# Schema_Proiect_v116.net
KiCad netlist of a schematic drawn in EAGLE
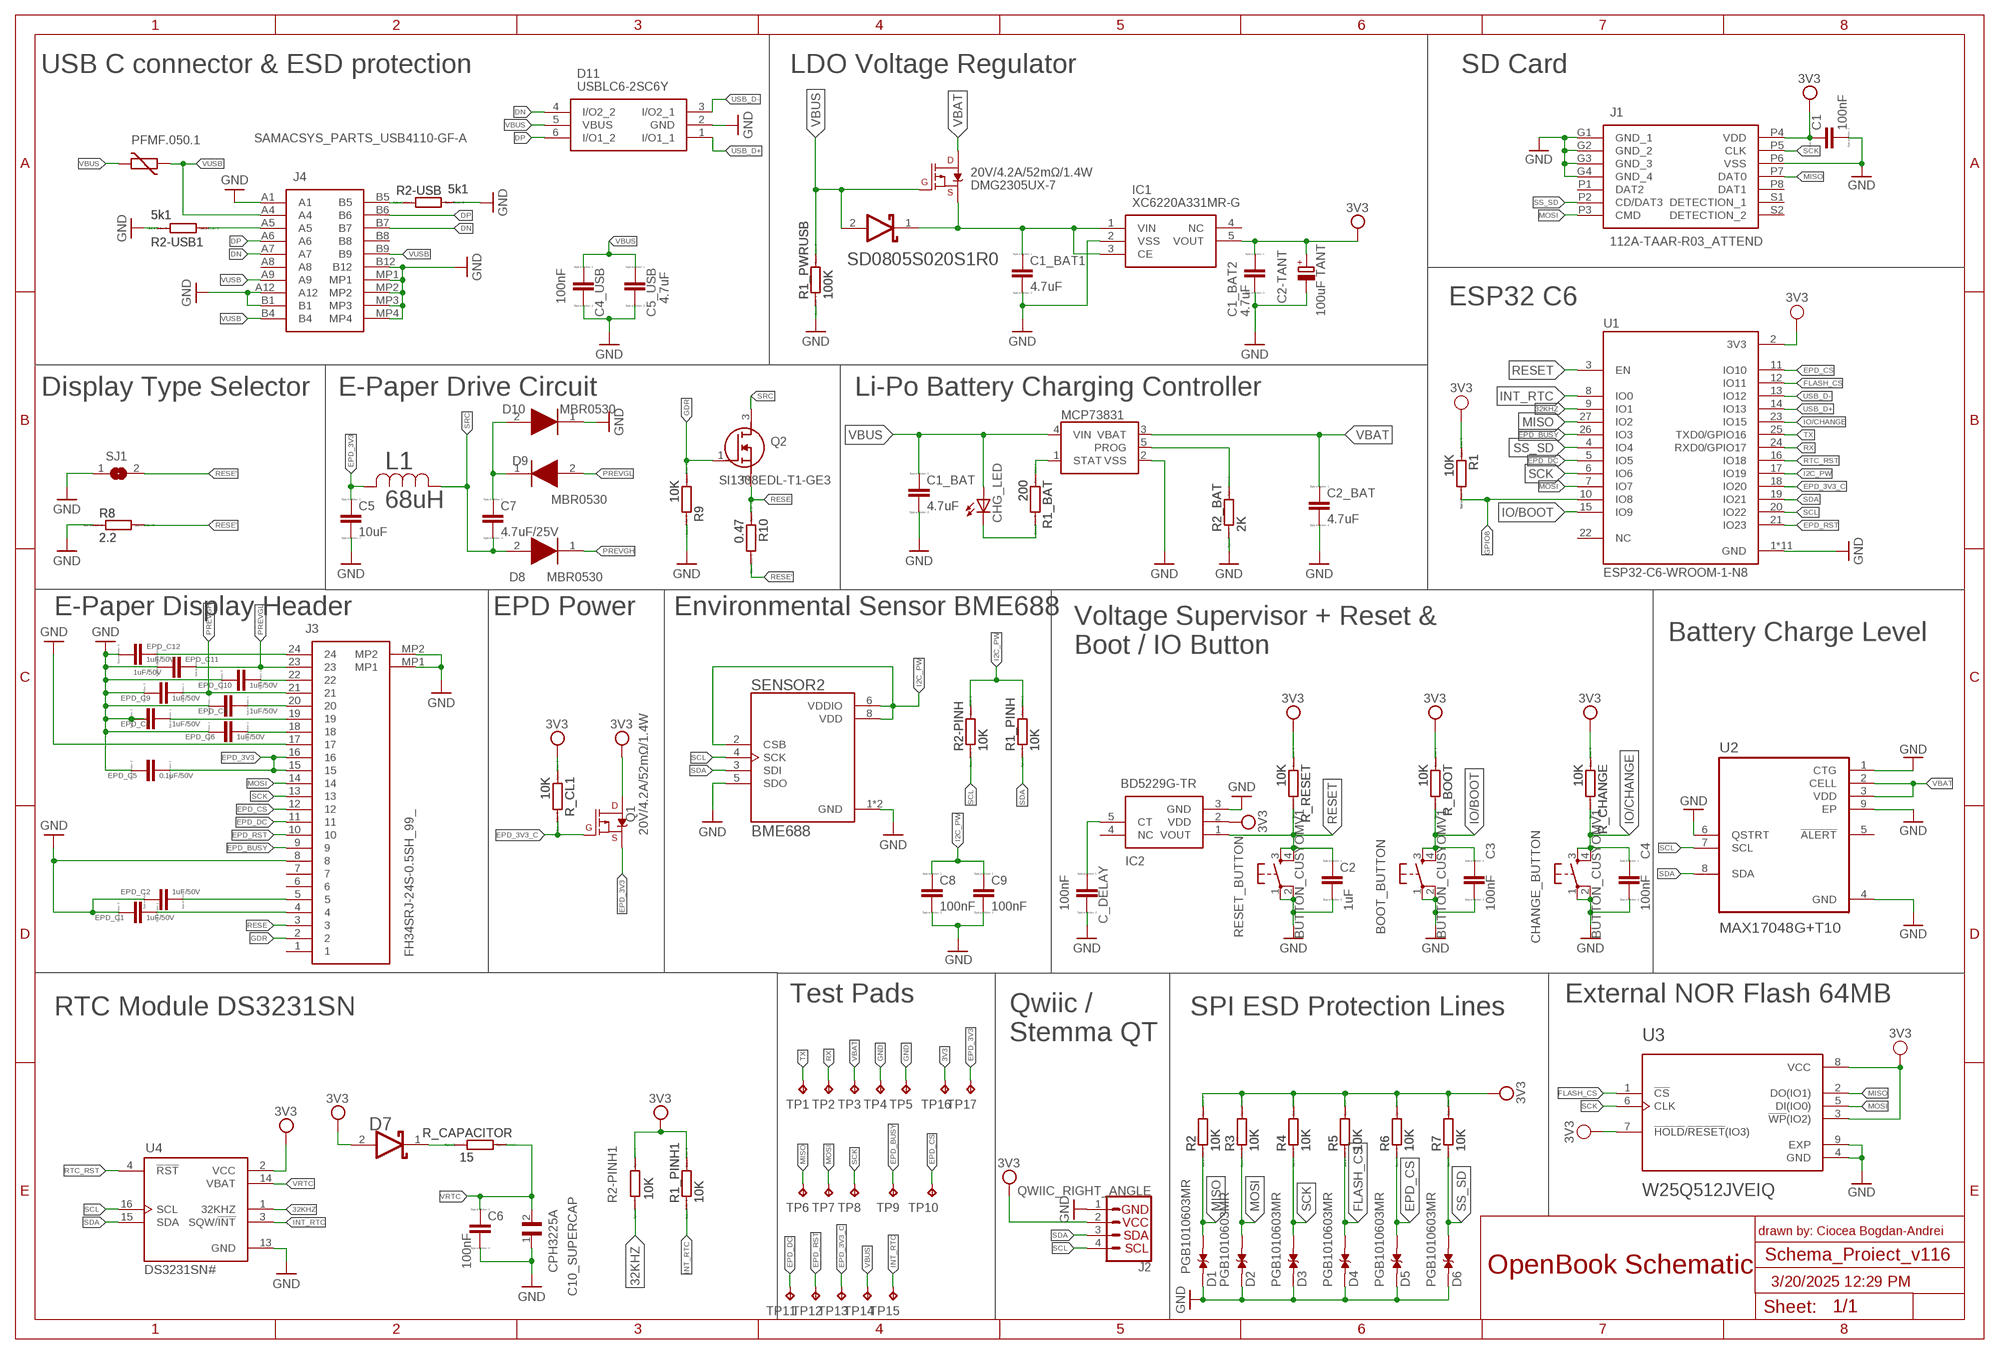
[diagram p0: schematic, sheet 1]

(export (version "E")
  (design (tool "Eeschema 10.0.6"))
  (components
    (comp (ref "BOOT_BUTTON")
      (value "BUTTON_CUSYOMV1")
      (footprint "eagle-import:MYBUTTON")
      (libsource (lib "eagle-import") (part "BUTTON_CUSYOMV1"))
    )
    (comp (ref "C1")
      (value "100nF")
      (footprint "eagle-import:EAGLE-LTSPICE_C0402")
      (libsource (lib "eagle-import") (part "EAGLE-LTSPICE_CC0402"))
    )
    (comp (ref "C1_BAT")
      (value "4.7uF")
      (footprint "eagle-import:EAGLE-LTSPICE_C0402")
      (libsource (lib "eagle-import") (part "EAGLE-LTSPICE_CC0402"))
    )
    (comp (ref "C1_BAT1")
      (value "4.7uF")
      (footprint "eagle-import:EAGLE-LTSPICE_C0402")
      (libsource (lib "eagle-import") (part "EAGLE-LTSPICE_CC0402"))
    )
    (comp (ref "C1_BAT2")
      (value "4.7uF")
      (footprint "eagle-import:EAGLE-LTSPICE_C0402")
      (libsource (lib "eagle-import") (part "EAGLE-LTSPICE_CC0402"))
    )
    (comp (ref "C2")
      (value "1uF")
      (footprint "eagle-import:EAGLE-LTSPICE_C0402")
      (libsource (lib "eagle-import") (part "EAGLE-LTSPICE_CC0402"))
    )
    (comp (ref "C2-TANT")
      (value "100uF TANT")
      (footprint "eagle-import:RCL_CT3528")
      (libsource (lib "eagle-import") (part "RCL_CPOL-EUCT3528"))
    )
    (comp (ref "C2_BAT")
      (value "4.7uF")
      (footprint "eagle-import:EAGLE-LTSPICE_C0402")
      (libsource (lib "eagle-import") (part "EAGLE-LTSPICE_CC0402"))
    )
    (comp (ref "C3")
      (value "100nF")
      (footprint "eagle-import:EAGLE-LTSPICE_C0402")
      (libsource (lib "eagle-import") (part "EAGLE-LTSPICE_CC0402"))
    )
    (comp (ref "C4")
      (value "100nF")
      (footprint "eagle-import:EAGLE-LTSPICE_C0402")
      (libsource (lib "eagle-import") (part "EAGLE-LTSPICE_CC0402"))
    )
    (comp (ref "C4_USB")
      (value "100nF")
      (footprint "eagle-import:EAGLE-LTSPICE_C0402")
      (libsource (lib "eagle-import") (part "EAGLE-LTSPICE_CC0402"))
    )
    (comp (ref "C5")
      (value "10uF")
      (footprint "eagle-import:EAGLE-LTSPICE_C0402")
      (libsource (lib "eagle-import") (part "EAGLE-LTSPICE_CC0402"))
    )
    (comp (ref "C5_USB")
      (value "4.7uF")
      (footprint "eagle-import:EAGLE-LTSPICE_C0402")
      (libsource (lib "eagle-import") (part "EAGLE-LTSPICE_CC0402"))
    )
    (comp (ref "C6")
      (value "100nF")
      (footprint "eagle-import:EAGLE-LTSPICE_C0402")
      (libsource (lib "eagle-import") (part "EAGLE-LTSPICE_CC0402"))
    )
    (comp (ref "C7")
      (value "4.7uF/25V")
      (footprint "eagle-import:EAGLE-LTSPICE_C0402")
      (libsource (lib "eagle-import") (part "EAGLE-LTSPICE_CC0402"))
    )
    (comp (ref "C8")
      (value "100nF")
      (footprint "eagle-import:EAGLE-LTSPICE_C0402")
      (libsource (lib "eagle-import") (part "EAGLE-LTSPICE_CC0402"))
    )
    (comp (ref "C9")
      (value "100nF")
      (footprint "eagle-import:EAGLE-LTSPICE_C0402")
      (libsource (lib "eagle-import") (part "EAGLE-LTSPICE_CC0402"))
    )
    (comp (ref "C10_SUPERCAP")
      (value "CPH3225A")
      (footprint "eagle-import:CAPCP3225X100N")
      (fields (field (name "MF") "Seiko Instruments"))
      (libsource (lib "eagle-import") (part "CPH3225A"))
    )
    (comp (ref "CHANGE_BUTTON")
      (value "BUTTON_CUSYOMV1")
      (footprint "eagle-import:MYBUTTON")
      (libsource (lib "eagle-import") (part "BUTTON_CUSYOMV1"))
    )
    (comp (ref "CHG_LED")
      (value "ADAFRUIT_LEDCHIP-LED0603")
      (footprint "eagle-import:ADAFRUIT_CHIP-LED0603")
      (libsource (lib "eagle-import") (part "ADAFRUIT_LEDCHIP-LED0603"))
    )
    (comp (ref "C_DELAY")
      (value "100nF")
      (footprint "eagle-import:EAGLE-LTSPICE_C0402")
      (libsource (lib "eagle-import") (part "EAGLE-LTSPICE_CC0402"))
    )
    (comp (ref "D1")
      (value "PGB1010603MR")
      (footprint "eagle-import:DIOC1608X36N")
      (fields (field (name "MF") "Littelfuse Inc."))
      (libsource (lib "eagle-import") (part "PGB1010603MR"))
    )
    (comp (ref "D2")
      (value "PGB1010603MR")
      (footprint "eagle-import:DIOC1608X36N")
      (fields (field (name "MF") "Littelfuse Inc."))
      (libsource (lib "eagle-import") (part "PGB1010603MR"))
    )
    (comp (ref "D3")
      (value "PGB1010603MR")
      (footprint "eagle-import:DIOC1608X36N")
      (fields (field (name "MF") "Littelfuse Inc."))
      (libsource (lib "eagle-import") (part "PGB1010603MR"))
    )
    (comp (ref "D4")
      (value "PGB1010603MR")
      (footprint "eagle-import:DIOC1608X36N")
      (fields (field (name "MF") "Littelfuse Inc."))
      (libsource (lib "eagle-import") (part "PGB1010603MR"))
    )
    (comp (ref "D5")
      (value "PGB1010603MR")
      (footprint "eagle-import:DIOC1608X36N")
      (fields (field (name "MF") "Littelfuse Inc."))
      (libsource (lib "eagle-import") (part "PGB1010603MR"))
    )
    (comp (ref "D6")
      (value "PGB1010603MR")
      (footprint "eagle-import:DIOC1608X36N")
      (fields (field (name "MF") "Littelfuse Inc."))
      (libsource (lib "eagle-import") (part "PGB1010603MR"))
    )
    (comp (ref "D7")
      (value "SD0805S020S1R0")
      (footprint "eagle-import:ESP32_WROVER_AVX---SD0805S020S1R0_AVX_SD0805S020S1R0_0")
      (fields
        (field (name "DIGIKEY_PART_NUMBER") "478-7800-1-ND")
        (field (name "MF") "AVX")
        (field (name "MOUSER_PART_NUMBER") "581-SD0805S020S1R0")
      )
      (libsource (lib "eagle-import") (part "ESP32_WROVER_AVX---SD0805S020S1R0_AVX_SD0805S020S1R0_0_0AVX_SD0805S020S1R0_0_0"))
    )
    (comp (ref "D8")
      (value "MBR0530")
      (footprint "eagle-import:SOD3716X135N")
      (fields (field (name "MF") "ON Semiconductor"))
      (libsource (lib "eagle-import") (part "MBR0530"))
    )
    (comp (ref "D9")
      (value "MBR0530")
      (footprint "eagle-import:SOD3716X135N")
      (fields (field (name "MF") "ON Semiconductor"))
      (libsource (lib "eagle-import") (part "MBR0530"))
    )
    (comp (ref "D10")
      (value "MBR0530")
      (footprint "eagle-import:SOD3716X135N")
      (fields (field (name "MF") "ON Semiconductor"))
      (libsource (lib "eagle-import") (part "MBR0530"))
    )
    (comp (ref "D11")
      (value "USBLC6-2SC6Y")
      (footprint "eagle-import:SOT95P280X145-6N")
      (fields (field (name "MF") "STMicroelectronics"))
      (libsource (lib "eagle-import") (part "USBLC6-2SC6Y"))
    )
    (comp (ref "DMG2305UX-7")
      (value "20V/4.2A/52mΩ/1.4W")
      (footprint "eagle-import:ESP32_WROVER_SPARKFUN-DISCRETESEMI_SOT23-3")
      (libsource (lib "eagle-import") (part "ESP32_WROVER_SPARKFUN-DISCRETESEMI_MOSFET_PCH-DMG2305UX-7"))
    )
    (comp (ref "EPD_C1")
      (value "1uF/50V")
      (footprint "eagle-import:EAGLE-LTSPICE_C0402")
      (libsource (lib "eagle-import") (part "EAGLE-LTSPICE_CC0402"))
    )
    (comp (ref "EPD_C2")
      (value "1uF/50V")
      (footprint "eagle-import:EAGLE-LTSPICE_C0402")
      (libsource (lib "eagle-import") (part "EAGLE-LTSPICE_CC0402"))
    )
    (comp (ref "EPD_C5")
      (value "0.1uF/50V")
      (footprint "eagle-import:EAGLE-LTSPICE_C0402")
      (libsource (lib "eagle-import") (part "EAGLE-LTSPICE_CC0402"))
    )
    (comp (ref "EPD_C6")
      (value "1uF/50V")
      (footprint "eagle-import:EAGLE-LTSPICE_C0402")
      (libsource (lib "eagle-import") (part "EAGLE-LTSPICE_CC0402"))
    )
    (comp (ref "EPD_C7")
      (value "1uF/50V")
      (footprint "eagle-import:EAGLE-LTSPICE_C0402")
      (libsource (lib "eagle-import") (part "EAGLE-LTSPICE_CC0402"))
    )
    (comp (ref "EPD_C8")
      (value "1uF/50V")
      (footprint "eagle-import:EAGLE-LTSPICE_C0402")
      (libsource (lib "eagle-import") (part "EAGLE-LTSPICE_CC0402"))
    )
    (comp (ref "EPD_C9")
      (value "1uF/50V")
      (footprint "eagle-import:EAGLE-LTSPICE_C0402")
      (libsource (lib "eagle-import") (part "EAGLE-LTSPICE_CC0402"))
    )
    (comp (ref "EPD_C10")
      (value "1uF/50V")
      (footprint "eagle-import:EAGLE-LTSPICE_C0402")
      (libsource (lib "eagle-import") (part "EAGLE-LTSPICE_CC0402"))
    )
    (comp (ref "EPD_C11")
      (value "1uF/50V")
      (footprint "eagle-import:EAGLE-LTSPICE_C0402")
      (libsource (lib "eagle-import") (part "EAGLE-LTSPICE_CC0402"))
    )
    (comp (ref "EPD_C12")
      (value "1uF/50V")
      (footprint "eagle-import:EAGLE-LTSPICE_C0402")
      (libsource (lib "eagle-import") (part "EAGLE-LTSPICE_CC0402"))
    )
    (comp (ref "IC1")
      (value "XC6220A331MR-G")
      (footprint "eagle-import:SOT95P280X120-5N")
      (fields (field (name "MOUSER_PART_NUMBER") "865-XC6220A331MR-G"))
      (libsource (lib "eagle-import") (part "XC6220A331MR-G"))
    )
    (comp (ref "IC2")
      (value "BD5229G-TR")
      (footprint "eagle-import:SOT95P280X125-5N")
      (fields (field (name "MOUSER_PART_NUMBER") "755-BD5229G-TR"))
      (libsource (lib "eagle-import") (part "BD5229G-TR"))
    )
    (comp (ref "J1")
      (value "112A-TAAR-R03_ATTEND")
      (footprint "eagle-import:112ATAARR03ATTEND")
      (fields (field (name "MANUFACTURER_PART_NUMBER") "112A-TAAR-R03 ATTEND"))
      (libsource (lib "eagle-import") (part "112A-TAAR-R03_ATTEND"))
    )
    (comp (ref "J2")
      (value "QWIIC_RIGHT_ANGLE")
      (footprint "eagle-import:JST04_1MM_RA")
      (libsource (lib "eagle-import") (part "QWIIC_CONNECTORJS-1MM"))
    )
    (comp (ref "J3")
      (value "FH34SRJ-24S-0.5SH_99_")
      (footprint "eagle-import:FH34SRJ24S05SH99")
      (fields
        (field (name "MANUFACTURER_PART_NUMBER") "FH34SRJ-24S-0.5SH(99)")
        (field (name "MOUSER_PART_NUMBER") "798-FH34SRJ24S05SH99")
      )
      (libsource (lib "eagle-import") (part "FH34SRJ-24S-0.5SH_99_"))
    )
    (comp (ref "J4")
      (value "SAMACSYS_PARTS_USB4110-GF-A")
      (footprint "eagle-import:SAMACSYS_PARTS_USB4110GFA")
      (fields
        (field (name "MANUFACTURER_PART_NUMBER") "USB4110-GF-A")
        (field (name "MOUSER_PART_NUMBER") "640-USB4110-GF-A")
      )
      (libsource (lib "eagle-import") (part "SAMACSYS_PARTS_USB4110-GF-A"))
    )
    (comp (ref "L1")
      (value "68uH")
      (footprint "eagle-import:IND_4828-WE-TPC_WRE")
      (fields
        (field (name "MANUFACTURER_PART_NUMBER") "744043680")
        (field (name "COPYRIGHT") "Copyright (C) 2024 Ultra Librarian. All rights reserved.")
      )
      (libsource (lib "eagle-import") (part "744043680IND_4828-WE-TPC_WRE"))
    )
    (comp (ref "MCP73831")
      (value "ESP32_WROVER_SPARKFUN-IC-POWER_MCP73831")
      (footprint "eagle-import:ESP32_WROVER_SPARKFUN-IC-POWER_SOT23-5")
      (libsource (lib "eagle-import") (part "ESP32_WROVER_SPARKFUN-IC-POWER_MCP73831"))
    )
    (comp (ref "PFMF.050.1")
      (value "ESP32C6_VARISTORCN1812")
      (footprint "eagle-import:ESP32C6_VARISTOR_CT_CN1812")
      (libsource (lib "eagle-import") (part "ESP32C6_VARISTORCN1812"))
    )
    (comp (ref "Q1")
      (value "20V/4.2A/52mΩ/1.4W")
      (footprint "eagle-import:ESP32_WROVER_SPARKFUN-DISCRETESEMI_SOT23-3")
      (libsource (lib "eagle-import") (part "ESP32_WROVER_SPARKFUN-DISCRETESEMI_MOSFET_PCH-DMG2305UX-7"))
    )
    (comp (ref "Q2")
      (value "SI1308EDL-T1-GE3")
      (footprint "eagle-import:SOT65P210X110-3N")
      (fields (field (name "MF") "Vishay Siliconix"))
      (libsource (lib "eagle-import") (part "SI1308EDL-T1-GE3"))
    )
    (comp (ref "R1")
      (value "10K")
      (footprint "eagle-import:ESP32_WROVER_EAGLE-LTSPICE_R0402")
      (libsource (lib "eagle-import") (part "ESP32_WROVER_EAGLE-LTSPICE_RR0402"))
    )
    (comp (ref "R1_BAT")
      (value "200")
      (footprint "eagle-import:ESP32_WROVER_EAGLE-LTSPICE_R0402")
      (libsource (lib "eagle-import") (part "ESP32_WROVER_EAGLE-LTSPICE_RR0402"))
    )
    (comp (ref "R1_PINH")
      (value "10K")
      (footprint "eagle-import:ESP32_WROVER_EAGLE-LTSPICE_R0402")
      (libsource (lib "eagle-import") (part "ESP32_WROVER_EAGLE-LTSPICE_RR0402"))
    )
    (comp (ref "R1_PINH1")
      (value "10K")
      (footprint "eagle-import:ESP32_WROVER_EAGLE-LTSPICE_R0402")
      (libsource (lib "eagle-import") (part "ESP32_WROVER_EAGLE-LTSPICE_RR0402"))
    )
    (comp (ref "R1_PWRUSB")
      (value "100K")
      (footprint "eagle-import:ESP32_WROVER_EAGLE-LTSPICE_R0402")
      (libsource (lib "eagle-import") (part "ESP32_WROVER_EAGLE-LTSPICE_RR0402"))
    )
    (comp (ref "R2")
      (value "10K")
      (footprint "eagle-import:ESP32_WROVER_EAGLE-LTSPICE_R0402")
      (libsource (lib "eagle-import") (part "ESP32_WROVER_EAGLE-LTSPICE_RR0402"))
    )
    (comp (ref "R2-PINH")
      (value "10K")
      (footprint "eagle-import:ESP32_WROVER_EAGLE-LTSPICE_R0402")
      (libsource (lib "eagle-import") (part "ESP32_WROVER_EAGLE-LTSPICE_RR0402"))
    )
    (comp (ref "R2-PINH1")
      (value "10K")
      (footprint "eagle-import:ESP32_WROVER_EAGLE-LTSPICE_R0402")
      (libsource (lib "eagle-import") (part "ESP32_WROVER_EAGLE-LTSPICE_RR0402"))
    )
    (comp (ref "R2-USB")
      (value "5k1")
      (footprint "eagle-import:ESP32_WROVER_EAGLE-LTSPICE_R0402")
      (libsource (lib "eagle-import") (part "ESP32_WROVER_EAGLE-LTSPICE_RR0402"))
    )
    (comp (ref "R2-USB1")
      (value "5k1")
      (footprint "eagle-import:ESP32_WROVER_EAGLE-LTSPICE_R0402")
      (libsource (lib "eagle-import") (part "ESP32_WROVER_EAGLE-LTSPICE_RR0402"))
    )
    (comp (ref "R2_BAT")
      (value "2K")
      (footprint "eagle-import:ESP32_WROVER_EAGLE-LTSPICE_R0402")
      (libsource (lib "eagle-import") (part "ESP32_WROVER_EAGLE-LTSPICE_RR0402"))
    )
    (comp (ref "R3")
      (value "10K")
      (footprint "eagle-import:ESP32_WROVER_EAGLE-LTSPICE_R0402")
      (libsource (lib "eagle-import") (part "ESP32_WROVER_EAGLE-LTSPICE_RR0402"))
    )
    (comp (ref "R4")
      (value "10K")
      (footprint "eagle-import:ESP32_WROVER_EAGLE-LTSPICE_R0402")
      (libsource (lib "eagle-import") (part "ESP32_WROVER_EAGLE-LTSPICE_RR0402"))
    )
    (comp (ref "R5")
      (value "10K")
      (footprint "eagle-import:ESP32_WROVER_EAGLE-LTSPICE_R0402")
      (libsource (lib "eagle-import") (part "ESP32_WROVER_EAGLE-LTSPICE_RR0402"))
    )
    (comp (ref "R6")
      (value "10K")
      (footprint "eagle-import:ESP32_WROVER_EAGLE-LTSPICE_R0402")
      (libsource (lib "eagle-import") (part "ESP32_WROVER_EAGLE-LTSPICE_RR0402"))
    )
    (comp (ref "R7")
      (value "10K")
      (footprint "eagle-import:ESP32_WROVER_EAGLE-LTSPICE_R0402")
      (libsource (lib "eagle-import") (part "ESP32_WROVER_EAGLE-LTSPICE_RR0402"))
    )
    (comp (ref "R8")
      (value "2.2")
      (footprint "eagle-import:ESP32_WROVER_EAGLE-LTSPICE_R0402")
      (libsource (lib "eagle-import") (part "ESP32_WROVER_EAGLE-LTSPICE_RR0402"))
    )
    (comp (ref "R9")
      (value "10K")
      (footprint "eagle-import:ESP32_WROVER_EAGLE-LTSPICE_R0402")
      (libsource (lib "eagle-import") (part "ESP32_WROVER_EAGLE-LTSPICE_RR0402"))
    )
    (comp (ref "R10")
      (value "0.47")
      (footprint "eagle-import:ESP32_WROVER_EAGLE-LTSPICE_R0402")
      (libsource (lib "eagle-import") (part "ESP32_WROVER_EAGLE-LTSPICE_RR0402"))
    )
    (comp (ref "RESET_BUTTON")
      (value "BUTTON_CUSYOMV1")
      (footprint "eagle-import:MYBUTTON")
      (libsource (lib "eagle-import") (part "BUTTON_CUSYOMV1"))
    )
    (comp (ref "R_BOOT")
      (value "10K")
      (footprint "eagle-import:ESP32_WROVER_EAGLE-LTSPICE_R0402")
      (libsource (lib "eagle-import") (part "ESP32_WROVER_EAGLE-LTSPICE_RR0402"))
    )
    (comp (ref "R_CAPACITOR")
      (value "15")
      (footprint "eagle-import:ESP32_WROVER_EAGLE-LTSPICE_R0402")
      (libsource (lib "eagle-import") (part "ESP32_WROVER_EAGLE-LTSPICE_RR0402"))
    )
    (comp (ref "R_CHANGE")
      (value "10K")
      (footprint "eagle-import:ESP32_WROVER_EAGLE-LTSPICE_R0402")
      (libsource (lib "eagle-import") (part "ESP32_WROVER_EAGLE-LTSPICE_RR0402"))
    )
    (comp (ref "R_CL1")
      (value "10K")
      (footprint "eagle-import:ESP32_WROVER_EAGLE-LTSPICE_R0402")
      (libsource (lib "eagle-import") (part "ESP32_WROVER_EAGLE-LTSPICE_RR0402"))
    )
    (comp (ref "R_RESET")
      (value "10K")
      (footprint "eagle-import:ESP32_WROVER_EAGLE-LTSPICE_R0402")
      (libsource (lib "eagle-import") (part "ESP32_WROVER_EAGLE-LTSPICE_RR0402"))
    )
    (comp (ref "SD0805S020S1R0")
      (value "ESP32_WROVER_AVX---SD0805S020S1R0_AVX_SD0805S020S1R0_0_0AVX_SD0805S020S1R0_0_0")
      (footprint "eagle-import:ESP32_WROVER_AVX---SD0805S020S1R0_AVX_SD0805S020S1R0_0")
      (fields
        (field (name "DIGIKEY_PART_NUMBER") "478-7800-1-ND")
        (field (name "MF") "AVX")
        (field (name "MOUSER_PART_NUMBER") "581-SD0805S020S1R0")
      )
      (libsource (lib "eagle-import") (part "ESP32_WROVER_AVX---SD0805S020S1R0_AVX_SD0805S020S1R0_0_0AVX_SD0805S020S1R0_0_0"))
    )
    (comp (ref "SENSOR2")
      (value "BME688")
      (footprint "eagle-import:ESP32_WROVER_BME680_PSON80P300X300X100-8N")
      (fields (field (name "MF") "Bosch Sensortec") (field (name "MP") "BME680"))
      (libsource (lib "eagle-import") (part "ESP32_WROVER_BME680_BME680"))
    )
    (comp (ref "SJ1") (value "SJ") (footprint "eagle-import:SJ") (libsource (lib "eagle-import") (part "SJ")))
    (comp (ref "TP1")
      (value "TX")
      (footprint "eagle-import:TP20R")
      (libsource (lib "eagle-import") (part "TPTP20R"))
    )
    (comp (ref "TP2")
      (value "RX")
      (footprint "eagle-import:TP20R")
      (libsource (lib "eagle-import") (part "TPTP20R"))
    )
    (comp (ref "TP3")
      (value "VBAT")
      (footprint "eagle-import:TP20R")
      (libsource (lib "eagle-import") (part "TPTP20R"))
    )
    (comp (ref "TP4")
      (value "GND")
      (footprint "eagle-import:TP20R")
      (libsource (lib "eagle-import") (part "TPTP20R"))
    )
    (comp (ref "TP5")
      (value "GND")
      (footprint "eagle-import:TP20R")
      (libsource (lib "eagle-import") (part "TPTP20R"))
    )
    (comp (ref "TP6")
      (value "MISO")
      (footprint "eagle-import:TP20R")
      (libsource (lib "eagle-import") (part "TPTP20R"))
    )
    (comp (ref "TP7")
      (value "MOSI")
      (footprint "eagle-import:TP20R")
      (libsource (lib "eagle-import") (part "TPTP20R"))
    )
    (comp (ref "TP8")
      (value "SCK")
      (footprint "eagle-import:TP20R")
      (libsource (lib "eagle-import") (part "TPTP20R"))
    )
    (comp (ref "TP9")
      (value "EPD_BUSY")
      (footprint "eagle-import:TP20R")
      (libsource (lib "eagle-import") (part "TPTP20R"))
    )
    (comp (ref "TP10")
      (value "EPD_CS")
      (footprint "eagle-import:TP20R")
      (libsource (lib "eagle-import") (part "TPTP20R"))
    )
    (comp (ref "TP11")
      (value "EPD_DC")
      (footprint "eagle-import:TP20R")
      (libsource (lib "eagle-import") (part "TPTP20R"))
    )
    (comp (ref "TP12")
      (value "EPD_RST")
      (footprint "eagle-import:TP20R")
      (libsource (lib "eagle-import") (part "TPTP20R"))
    )
    (comp (ref "TP13")
      (value "EPD_3V3_C")
      (footprint "eagle-import:TP20R")
      (libsource (lib "eagle-import") (part "TPTP20R"))
    )
    (comp (ref "TP14")
      (value "VBUS")
      (footprint "eagle-import:TP20R")
      (libsource (lib "eagle-import") (part "TPTP20R"))
    )
    (comp (ref "TP15")
      (value "INT_RTC")
      (footprint "eagle-import:TP20R")
      (libsource (lib "eagle-import") (part "TPTP20R"))
    )
    (comp (ref "TP16")
      (value "3V3")
      (footprint "eagle-import:TP20R")
      (libsource (lib "eagle-import") (part "TPTP20R"))
    )
    (comp (ref "TP17")
      (value "EPD_3V3")
      (footprint "eagle-import:TP20R")
      (libsource (lib "eagle-import") (part "TPTP20R"))
    )
    (comp (ref "U1")
      (value "ESP32-C6-WROOM-1-N8")
      (footprint "eagle-import:XCVR_ESP32-C6-WROOM-1-N8")
      (fields (field (name "MF") "Espressif Systems"))
      (libsource (lib "eagle-import") (part "ESP32-C6-WROOM-1-N8"))
    )
    (comp (ref "U2")
      (value "MAX17048G+T10")
      (footprint "eagle-import:SON50P200X200X80-9N")
      (fields (field (name "MF") "Analog Devices"))
      (libsource (lib "eagle-import") (part "MAX17048G+T10"))
    )
    (comp (ref "U3")
      (value "W25Q512JVEIQ")
      (footprint "eagle-import:SON127P600X800X80-9N")
      (fields (field (name "MF") "Winbond Electronics"))
      (libsource (lib "eagle-import") (part "W25Q512JVEIQ"))
    )
    (comp (ref "U4")
      (value "DS3231SN#")
      (footprint "eagle-import:SOIC127P1032X265-16N")
      (fields (field (name "MF") "Analog Devices"))
      (libsource (lib "eagle-import") (part "DS3231SN#"))
    )
  )
  (nets
    (net (code "1") (name "3V3") (class "Default")
      (node (ref "C1") (pin "1") (pinfunction "1_1") (pintype "passive"))
      (node (ref "C1_BAT2") (pin "1") (pinfunction "1_1") (pintype "passive"))
      (node (ref "C2-TANT") (pin "+") (pinfunction "+_+") (pintype "passive"))
      (node (ref "D7") (pin "2") (pinfunction "ANODE_2") (pintype "bidirectional"))
      (node (ref "IC1") (pin "5") (pinfunction "VOUT_5") (pintype "bidirectional"))
      (node (ref "IC2") (pin "2") (pinfunction "VDD_2") (pintype "bidirectional"))
      (node (ref "J1") (pin "P4") (pinfunction "VDD_P4") (pintype "bidirectional"))
      (node (ref "J2") (pin "2") (pinfunction "2_2") (pintype "power_in"))
      (node (ref "Q1") (pin "3") (pinfunction "D_3") (pintype "bidirectional"))
      (node (ref "R1") (pin "1") (pinfunction "1_1") (pintype "passive"))
      (node (ref "R1_PINH1") (pin "2") (pinfunction "2_2") (pintype "passive"))
      (node (ref "R2") (pin "2") (pinfunction "2_2") (pintype "passive"))
      (node (ref "R2-PINH1") (pin "1") (pinfunction "1_1") (pintype "passive"))
      (node (ref "R3") (pin "2") (pinfunction "2_2") (pintype "passive"))
      (node (ref "R4") (pin "2") (pinfunction "2_2") (pintype "passive"))
      (node (ref "R5") (pin "2") (pinfunction "2_2") (pintype "passive"))
      (node (ref "R6") (pin "2") (pinfunction "2_2") (pintype "passive"))
      (node (ref "R7") (pin "2") (pinfunction "2_2") (pintype "passive"))
      (node (ref "R_BOOT") (pin "1") (pinfunction "1_1") (pintype "passive"))
      (node (ref "R_CHANGE") (pin "1") (pinfunction "1_1") (pintype "passive"))
      (node (ref "R_CL1") (pin "1") (pinfunction "1_1") (pintype "passive"))
      (node (ref "R_RESET") (pin "1") (pinfunction "1_1") (pintype "passive"))
      (node (ref "TP16") (pin "TP") (pinfunction "TP_TP") (pintype "input"))
      (node (ref "U1") (pin "2") (pinfunction "3V3_2") (pintype "power_in"))
      (node (ref "U3") (pin "3") (pinfunction "~{WP}(IO2)_3") (pintype "bidirectional"))
      (node (ref "U3") (pin "7") (pinfunction "~{HOLD}/~{RESET}(IO3)_7") (pintype "bidirectional"))
      (node (ref "U3") (pin "8") (pinfunction "VCC_8") (pintype "power_in"))
      (node (ref "U4") (pin "2") (pinfunction "VCC_2") (pintype "power_in"))
    )
    (net (code "2") (name "32KHZ") (class "Default")
      (node (ref "R2-PINH1") (pin "2") (pinfunction "2_2") (pintype "passive"))
      (node (ref "U1") (pin "9") (pinfunction "IO1_9") (pintype "bidirectional"))
      (node (ref "U4") (pin "1") (pinfunction "32KHZ_1") (pintype "output"))
    )
    (net (code "3") (name "DN") (class "Default")
      (node (ref "D11") (pin "4") (pinfunction "I/O2_2_4") (pintype "bidirectional"))
      (node (ref "J4") (pin "A7") (pinfunction "A7_A7") (pintype "bidirectional"))
      (node (ref "J4") (pin "B7") (pinfunction "B7_B7") (pintype "bidirectional"))
    )
    (net (code "4") (name "DP") (class "Default")
      (node (ref "D11") (pin "6") (pinfunction "I/O1_2_6") (pintype "bidirectional"))
      (node (ref "J4") (pin "A6") (pinfunction "A6_A6") (pintype "bidirectional"))
      (node (ref "J4") (pin "B6") (pinfunction "B6_B6") (pintype "bidirectional"))
    )
    (net (code "5") (name "EPD_3V3") (class "Default")
      (node (ref "C5") (pin "1") (pinfunction "1_1") (pintype "passive"))
      (node (ref "EPD_C5") (pin "1") (pinfunction "1_1") (pintype "passive"))
      (node (ref "J3") (pin "15") (pinfunction "15_15") (pintype "bidirectional"))
      (node (ref "J3") (pin "16") (pinfunction "16_16") (pintype "bidirectional"))
      (node (ref "L1") (pin "2") (pinfunction "2_2") (pintype "passive"))
      (node (ref "Q1") (pin "2") (pinfunction "S_2") (pintype "bidirectional"))
      (node (ref "TP17") (pin "TP") (pinfunction "TP_TP") (pintype "input"))
    )
    (net (code "6") (name "EPD_3V3_C") (class "Default")
      (node (ref "Q1") (pin "1") (pinfunction "G_1") (pintype "bidirectional"))
      (node (ref "R_CL1") (pin "2") (pinfunction "2_2") (pintype "passive"))
      (node (ref "TP13") (pin "TP") (pinfunction "TP_TP") (pintype "input"))
      (node (ref "U1") (pin "18") (pinfunction "IO20_18") (pintype "bidirectional"))
    )
    (net (code "7") (name "EPD_BUSY") (class "Default")
      (node (ref "J3") (pin "9") (pinfunction "9_9") (pintype "bidirectional"))
      (node (ref "TP9") (pin "TP") (pinfunction "TP_TP") (pintype "input"))
      (node (ref "U1") (pin "26") (pinfunction "IO3_26") (pintype "bidirectional"))
    )
    (net (code "8") (name "EPD_CS") (class "Default")
      (node (ref "D5") (pin "2") (pinfunction "2_2") (pintype "passive"))
      (node (ref "J3") (pin "12") (pinfunction "12_12") (pintype "bidirectional"))
      (node (ref "R6") (pin "1") (pinfunction "1_1") (pintype "passive"))
      (node (ref "TP10") (pin "TP") (pinfunction "TP_TP") (pintype "input"))
      (node (ref "U1") (pin "11") (pinfunction "IO10_11") (pintype "bidirectional"))
    )
    (net (code "9") (name "EPD_DC") (class "Default")
      (node (ref "J3") (pin "11") (pinfunction "11_11") (pintype "bidirectional"))
      (node (ref "TP11") (pin "TP") (pinfunction "TP_TP") (pintype "input"))
      (node (ref "U1") (pin "5") (pinfunction "IO5_5") (pintype "bidirectional"))
    )
    (net (code "10") (name "EPD_RST") (class "Default")
      (node (ref "J3") (pin "10") (pinfunction "10_10") (pintype "bidirectional"))
      (node (ref "TP12") (pin "TP") (pinfunction "TP_TP") (pintype "input"))
      (node (ref "U1") (pin "21") (pinfunction "IO23_21") (pintype "bidirectional"))
    )
    (net (code "11") (name "FLASH_CS") (class "Default")
      (node (ref "D4") (pin "2") (pinfunction "2_2") (pintype "passive"))
      (node (ref "R5") (pin "1") (pinfunction "1_1") (pintype "passive"))
      (node (ref "U1") (pin "12") (pinfunction "IO11_12") (pintype "bidirectional"))
      (node (ref "U3") (pin "1") (pinfunction "~{CS}_1") (pintype "input"))
    )
    (net (code "12") (name "GDR") (class "Default")
      (node (ref "J3") (pin "2") (pinfunction "2_2") (pintype "bidirectional"))
      (node (ref "Q2") (pin "1") (pinfunction "G_1") (pintype "bidirectional"))
      (node (ref "R9") (pin "1") (pinfunction "1_1") (pintype "passive"))
    )
    (net (code "13") (name "GND") (class "Default")
      (node (ref "BOOT_BUTTON") (pin "1") (pinfunction "1_1") (pintype "passive"))
      (node (ref "BOOT_BUTTON") (pin "2") (pinfunction "2_2") (pintype "passive"))
      (node (ref "C1") (pin "2") (pinfunction "2_2") (pintype "passive"))
      (node (ref "C10_SUPERCAP") (pin "1") (pinfunction "1_1") (pintype "passive"))
      (node (ref "C1_BAT") (pin "2") (pinfunction "2_2") (pintype "passive"))
      (node (ref "C1_BAT1") (pin "2") (pinfunction "2_2") (pintype "passive"))
      (node (ref "C1_BAT2") (pin "2") (pinfunction "2_2") (pintype "passive"))
      (node (ref "C2") (pin "2") (pinfunction "2_2") (pintype "passive"))
      (node (ref "C2-TANT") (pin "-") (pinfunction "-_-") (pintype "passive"))
      (node (ref "C2_BAT") (pin "2") (pinfunction "2_2") (pintype "passive"))
      (node (ref "C3") (pin "2") (pinfunction "2_2") (pintype "passive"))
      (node (ref "C4") (pin "2") (pinfunction "2_2") (pintype "passive"))
      (node (ref "C4_USB") (pin "2") (pinfunction "2_2") (pintype "passive"))
      (node (ref "C5") (pin "2") (pinfunction "2_2") (pintype "passive"))
      (node (ref "C5_USB") (pin "2") (pinfunction "2_2") (pintype "passive"))
      (node (ref "C6") (pin "2") (pinfunction "2_2") (pintype "passive"))
      (node (ref "C8") (pin "2") (pinfunction "2_2") (pintype "passive"))
      (node (ref "C9") (pin "2") (pinfunction "2_2") (pintype "passive"))
      (node (ref "CHANGE_BUTTON") (pin "1") (pinfunction "1_1") (pintype "passive"))
      (node (ref "CHANGE_BUTTON") (pin "2") (pinfunction "2_2") (pintype "passive"))
      (node (ref "C_DELAY") (pin "2") (pinfunction "2_2") (pintype "passive"))
      (node (ref "D1") (pin "1") (pinfunction "1_1") (pintype "passive"))
      (node (ref "D10") (pin "1") (pinfunction "K_1") (pintype "bidirectional"))
      (node (ref "D11") (pin "2") (pinfunction "GND_2") (pintype "bidirectional"))
      (node (ref "D2") (pin "1") (pinfunction "1_1") (pintype "passive"))
      (node (ref "D3") (pin "1") (pinfunction "1_1") (pintype "passive"))
      (node (ref "D4") (pin "1") (pinfunction "1_1") (pintype "passive"))
      (node (ref "D5") (pin "1") (pinfunction "1_1") (pintype "passive"))
      (node (ref "D6") (pin "1") (pinfunction "1_1") (pintype "passive"))
      (node (ref "EPD_C1") (pin "2") (pinfunction "2_2") (pintype "passive"))
      (node (ref "EPD_C10") (pin "2") (pinfunction "2_2") (pintype "passive"))
      (node (ref "EPD_C11") (pin "2") (pinfunction "2_2") (pintype "passive"))
      (node (ref "EPD_C12") (pin "2") (pinfunction "2_2") (pintype "passive"))
      (node (ref "EPD_C2") (pin "2") (pinfunction "2_2") (pintype "passive"))
      (node (ref "EPD_C5") (pin "2") (pinfunction "2_2") (pintype "passive"))
      (node (ref "EPD_C6") (pin "2") (pinfunction "2_2") (pintype "passive"))
      (node (ref "EPD_C7") (pin "2") (pinfunction "2_2") (pintype "passive"))
      (node (ref "EPD_C8") (pin "2") (pinfunction "2_2") (pintype "passive"))
      (node (ref "EPD_C9") (pin "2") (pinfunction "2_2") (pintype "passive"))
      (node (ref "IC1") (pin "2") (pinfunction "VSS_2") (pintype "bidirectional"))
      (node (ref "IC2") (pin "3") (pinfunction "GND_3") (pintype "bidirectional"))
      (node (ref "J1") (pin "G1") (pinfunction "GND_1_G1") (pintype "bidirectional"))
      (node (ref "J1") (pin "G2") (pinfunction "GND_2_G2") (pintype "bidirectional"))
      (node (ref "J1") (pin "G3") (pinfunction "GND_3_G3") (pintype "bidirectional"))
      (node (ref "J1") (pin "G4") (pinfunction "GND_4_G4") (pintype "bidirectional"))
      (node (ref "J1") (pin "P6") (pinfunction "VSS_P6") (pintype "bidirectional"))
      (node (ref "J2") (pin "1") (pinfunction "1_1") (pintype "power_in"))
      (node (ref "J3") (pin "17") (pinfunction "17_17") (pintype "bidirectional"))
      (node (ref "J3") (pin "8") (pinfunction "8_8") (pintype "bidirectional"))
      (node (ref "J3") (pin "MP1") (pinfunction "MP1_MP1") (pintype "bidirectional"))
      (node (ref "J3") (pin "MP2") (pinfunction "MP2_MP2") (pintype "bidirectional"))
      (node (ref "J4") (pin "A1") (pinfunction "A1_A1") (pintype "bidirectional"))
      (node (ref "J4") (pin "A12") (pinfunction "A12_A12") (pintype "bidirectional"))
      (node (ref "J4") (pin "B1") (pinfunction "B1_B1") (pintype "bidirectional"))
      (node (ref "J4") (pin "B12") (pinfunction "B12_B12") (pintype "bidirectional"))
      (node (ref "J4") (pin "MP1") (pinfunction "MP1_MP1") (pintype "bidirectional"))
      (node (ref "J4") (pin "MP2") (pinfunction "MP2_MP2") (pintype "bidirectional"))
      (node (ref "J4") (pin "MP3") (pinfunction "MP3_MP3") (pintype "bidirectional"))
      (node (ref "J4") (pin "MP4") (pinfunction "MP4_MP4") (pintype "bidirectional"))
      (node (ref "MCP73831") (pin "2") (pinfunction "VSS_2") (pintype "power_in"))
      (node (ref "R1_PWRUSB") (pin "1") (pinfunction "1_1") (pintype "passive"))
      (node (ref "R2-USB") (pin "2") (pinfunction "2_2") (pintype "passive"))
      (node (ref "R2-USB1") (pin "1") (pinfunction "1_1") (pintype "passive"))
      (node (ref "R2_BAT") (pin "1") (pinfunction "1_1") (pintype "passive"))
      (node (ref "R8") (pin "1") (pinfunction "1_1") (pintype "passive"))
      (node (ref "R9") (pin "2") (pinfunction "2_2") (pintype "passive"))
      (node (ref "RESET_BUTTON") (pin "1") (pinfunction "1_1") (pintype "passive"))
      (node (ref "RESET_BUTTON") (pin "2") (pinfunction "2_2") (pintype "passive"))
      (node (ref "SENSOR2") (pin "1") (pinfunction "GND_1") (pintype "power_in"))
      (node (ref "SENSOR2") (pin "5") (pinfunction "SDO_5") (pintype "bidirectional"))
      (node (ref "SENSOR2") (pin "7") (pinfunction "GND_7") (pintype "power_in"))
      (node (ref "SJ1") (pin "1") (pinfunction "1_1") (pintype "passive"))
      (node (ref "TP4") (pin "TP") (pinfunction "TP_TP") (pintype "input"))
      (node (ref "TP5") (pin "TP") (pinfunction "TP_TP") (pintype "input"))
      (node (ref "U1") (pin "1") (pinfunction "GND_1") (pintype "power_in"))
      (node (ref "U1") (pin "28") (pinfunction "GND_28") (pintype "power_in"))
      (node (ref "U1") (pin "29_1") (pinfunction "GND_29_1") (pintype "power_in"))
      (node (ref "U1") (pin "29_2") (pinfunction "GND_29_2") (pintype "power_in"))
      (node (ref "U1") (pin "29_3") (pinfunction "GND_29_3") (pintype "power_in"))
      (node (ref "U1") (pin "29_4") (pinfunction "GND_29_4") (pintype "power_in"))
      (node (ref "U1") (pin "29_5") (pinfunction "GND_29_5") (pintype "power_in"))
      (node (ref "U1") (pin "29_6") (pinfunction "GND_29_6") (pintype "power_in"))
      (node (ref "U1") (pin "29_7") (pinfunction "GND_29_7") (pintype "power_in"))
      (node (ref "U1") (pin "29_8") (pinfunction "GND_29_8") (pintype "power_in"))
      (node (ref "U1") (pin "29_9") (pinfunction "GND_29_9") (pintype "power_in"))
      (node (ref "U2") (pin "1") (pinfunction "CTG_1") (pintype "power_in"))
      (node (ref "U2") (pin "4") (pinfunction "GND_4") (pintype "power_in"))
      (node (ref "U2") (pin "6") (pinfunction "QSTRT_6") (pintype "input"))
      (node (ref "U2") (pin "9") (pinfunction "EP_9") (pintype "power_in"))
      (node (ref "U3") (pin "4") (pinfunction "GND_4") (pintype "power_in"))
      (node (ref "U3") (pin "9") (pinfunction "EXP_9") (pintype "passive"))
      (node (ref "U4") (pin "13") (pinfunction "GND_13") (pintype "power_in"))
    )
    (net (code "14") (name "GPIO8") (class "Default")
      (node (ref "R1") (pin "2") (pinfunction "2_2") (pintype "passive"))
      (node (ref "U1") (pin "10") (pinfunction "IO8_10") (pintype "bidirectional"))
    )
    (net (code "15") (name "I2C_PW") (class "Default")
      (node (ref "C8") (pin "1") (pinfunction "1_1") (pintype "passive"))
      (node (ref "C9") (pin "1") (pinfunction "1_1") (pintype "passive"))
      (node (ref "R1_PINH") (pin "2") (pinfunction "2_2") (pintype "passive"))
      (node (ref "R2-PINH") (pin "2") (pinfunction "2_2") (pintype "passive"))
      (node (ref "SENSOR2") (pin "2") (pinfunction "CSB_2") (pintype "input"))
      (node (ref "SENSOR2") (pin "6") (pinfunction "VDDIO_6") (pintype "power_in"))
      (node (ref "SENSOR2") (pin "8") (pinfunction "VDD_8") (pintype "power_in"))
      (node (ref "U1") (pin "17") (pinfunction "IO19_17") (pintype "bidirectional"))
    )
    (net (code "16") (name "INT_RTC") (class "Default")
      (node (ref "R1_PINH1") (pin "1") (pinfunction "1_1") (pintype "passive"))
      (node (ref "TP15") (pin "TP") (pinfunction "TP_TP") (pintype "input"))
      (node (ref "U1") (pin "8") (pinfunction "IO0_8") (pintype "bidirectional"))
      (node (ref "U4") (pin "3") (pinfunction "SQW/~{INT}_3") (pintype "output"))
    )
    (net (code "17") (name "IO{slash}BOOT") (class "Default")
      (node (ref "BOOT_BUTTON") (pin "3") (pinfunction "3_3") (pintype "passive"))
      (node (ref "BOOT_BUTTON") (pin "4") (pinfunction "4_4") (pintype "passive"))
      (node (ref "C3") (pin "1") (pinfunction "1_1") (pintype "passive"))
      (node (ref "R_BOOT") (pin "2") (pinfunction "2_2") (pintype "passive"))
      (node (ref "U1") (pin "15") (pinfunction "IO9_15") (pintype "bidirectional"))
    )
    (net (code "18") (name "IO{slash}CHANGE") (class "Default")
      (node (ref "C4") (pin "1") (pinfunction "1_1") (pintype "passive"))
      (node (ref "CHANGE_BUTTON") (pin "3") (pinfunction "3_3") (pintype "passive"))
      (node (ref "CHANGE_BUTTON") (pin "4") (pinfunction "4_4") (pintype "passive"))
      (node (ref "R_CHANGE") (pin "2") (pinfunction "2_2") (pintype "passive"))
      (node (ref "U1") (pin "23") (pinfunction "IO15_23") (pintype "bidirectional"))
    )
    (net (code "19") (name "MISO") (class "Default")
      (node (ref "D1") (pin "2") (pinfunction "2_2") (pintype "passive"))
      (node (ref "J1") (pin "P7") (pinfunction "DAT0_P7") (pintype "bidirectional"))
      (node (ref "R2") (pin "1") (pinfunction "1_1") (pintype "passive"))
      (node (ref "TP6") (pin "TP") (pinfunction "TP_TP") (pintype "input"))
      (node (ref "U1") (pin "27") (pinfunction "IO2_27") (pintype "bidirectional"))
      (node (ref "U3") (pin "2") (pinfunction "DO(IO1)_2") (pintype "bidirectional"))
    )
    (net (code "20") (name "MOSI") (class "Default")
      (node (ref "D2") (pin "2") (pinfunction "2_2") (pintype "passive"))
      (node (ref "J1") (pin "P3") (pinfunction "CMD_P3") (pintype "bidirectional"))
      (node (ref "J3") (pin "14") (pinfunction "14_14") (pintype "bidirectional"))
      (node (ref "R3") (pin "1") (pinfunction "1_1") (pintype "passive"))
      (node (ref "TP7") (pin "TP") (pinfunction "TP_TP") (pintype "input"))
      (node (ref "U1") (pin "7") (pinfunction "IO7_7") (pintype "bidirectional"))
      (node (ref "U3") (pin "5") (pinfunction "DI(IO0)_5") (pintype "bidirectional"))
    )
    (net (code "21") (name "Net-(CHG_LED-PadC)") (class "Default")
      (node (ref "CHG_LED") (pin "C") (pinfunction "C_C") (pintype "passive"))
      (node (ref "R1_BAT") (pin "2") (pinfunction "2_2") (pintype "passive"))
    )
    (net (code "22") (name "Net-(D7-CATHODE)") (class "Default")
      (node (ref "D7") (pin "1") (pinfunction "CATHODE_1") (pintype "bidirectional"))
      (node (ref "R_CAPACITOR") (pin "2") (pinfunction "2_2") (pintype "passive"))
    )
    (net (code "23") (name "Net-(D10-A)") (class "Default")
      (node (ref "C7") (pin "1") (pinfunction "1_1") (pintype "passive"))
      (node (ref "D10") (pin "2") (pinfunction "A_2") (pintype "bidirectional"))
      (node (ref "D9") (pin "1") (pinfunction "K_1") (pintype "bidirectional"))
    )
    (net (code "24") (name "Net-(DMG2305UX-7-S)") (class "Default")
      (node (ref "C1_BAT1") (pin "1") (pinfunction "1_1") (pintype "passive"))
      (node (ref "DMG2305UX-7") (pin "2") (pinfunction "S_2") (pintype "bidirectional"))
      (node (ref "IC1") (pin "1") (pinfunction "VIN_1") (pintype "bidirectional"))
      (node (ref "IC1") (pin "3") (pinfunction "CE_3") (pintype "bidirectional"))
      (node (ref "SD0805S020S1R0") (pin "1") (pinfunction "CATHODE_1") (pintype "bidirectional"))
    )
    (net (code "25") (name "Net-(EPD_C1-Pad1)") (class "Default")
      (node (ref "EPD_C1") (pin "1") (pinfunction "1_1") (pintype "passive"))
      (node (ref "J3") (pin "4") (pinfunction "4_4") (pintype "bidirectional"))
    )
    (net (code "26") (name "Net-(EPD_C2-Pad1)") (class "Default")
      (node (ref "EPD_C2") (pin "1") (pinfunction "1_1") (pintype "passive"))
      (node (ref "J3") (pin "5") (pinfunction "5_5") (pintype "bidirectional"))
    )
    (net (code "27") (name "Net-(EPD_C6-Pad1)") (class "Default")
      (node (ref "EPD_C6") (pin "1") (pinfunction "1_1") (pintype "passive"))
      (node (ref "J3") (pin "18") (pinfunction "18_18") (pintype "bidirectional"))
    )
    (net (code "28") (name "Net-(EPD_C7-Pad1)") (class "Default")
      (node (ref "EPD_C7") (pin "1") (pinfunction "1_1") (pintype "passive"))
      (node (ref "J3") (pin "19") (pinfunction "19_19") (pintype "bidirectional"))
    )
    (net (code "29") (name "Net-(EPD_C8-Pad1)") (class "Default")
      (node (ref "EPD_C8") (pin "1") (pinfunction "1_1") (pintype "passive"))
      (node (ref "J3") (pin "20") (pinfunction "20_20") (pintype "bidirectional"))
    )
    (net (code "30") (name "Net-(EPD_C10-Pad1)") (class "Default")
      (node (ref "EPD_C10") (pin "1") (pinfunction "1_1") (pintype "passive"))
      (node (ref "J3") (pin "22") (pinfunction "22_22") (pintype "bidirectional"))
    )
    (net (code "31") (name "Net-(EPD_C12-Pad1)") (class "Default")
      (node (ref "EPD_C12") (pin "1") (pinfunction "1_1") (pintype "passive"))
      (node (ref "J3") (pin "24") (pinfunction "24_24") (pintype "bidirectional"))
    )
    (net (code "32") (name "Net-(IC2-CT)") (class "Default")
      (node (ref "C_DELAY") (pin "1") (pinfunction "1_1") (pintype "passive"))
      (node (ref "IC2") (pin "5") (pinfunction "CT_5") (pintype "bidirectional"))
    )
    (net (code "33") (name "Net-(J4-PadA5)") (class "Default")
      (node (ref "J4") (pin "A5") (pinfunction "A5_A5") (pintype "bidirectional"))
      (node (ref "R2-USB1") (pin "2") (pinfunction "2_2") (pintype "passive"))
    )
    (net (code "34") (name "Net-(J4-PadB5)") (class "Default")
      (node (ref "J4") (pin "B5") (pinfunction "B5_B5") (pintype "bidirectional"))
      (node (ref "R2-USB") (pin "1") (pinfunction "1_1") (pintype "passive"))
    )
    (net (code "35") (name "Net-(MCP73831-PROG)") (class "Default")
      (node (ref "MCP73831") (pin "5") (pinfunction "PROG_5") (pintype "input"))
      (node (ref "R2_BAT") (pin "2") (pinfunction "2_2") (pintype "passive"))
    )
    (net (code "36") (name "Net-(MCP73831-STAT)") (class "Default")
      (node (ref "MCP73831") (pin "1") (pinfunction "STAT_1") (pintype "output"))
      (node (ref "R1_BAT") (pin "1") (pinfunction "1_1") (pintype "passive"))
    )
    (net (code "37") (name "PREVGH") (class "Default")
      (node (ref "D8") (pin "1") (pinfunction "K_1") (pintype "bidirectional"))
      (node (ref "EPD_C9") (pin "1") (pinfunction "1_1") (pintype "passive"))
      (node (ref "J3") (pin "21") (pinfunction "21_21") (pintype "bidirectional"))
    )
    (net (code "38") (name "PREVGL") (class "Default")
      (node (ref "D9") (pin "2") (pinfunction "A_2") (pintype "bidirectional"))
      (node (ref "EPD_C11") (pin "1") (pinfunction "1_1") (pintype "passive"))
      (node (ref "J3") (pin "23") (pinfunction "23_23") (pintype "bidirectional"))
    )
    (net (code "39") (name "RESE") (class "Default")
      (node (ref "J3") (pin "3") (pinfunction "3_3") (pintype "bidirectional"))
      (node (ref "Q2") (pin "2") (pinfunction "S_2") (pintype "bidirectional"))
      (node (ref "R10") (pin "1") (pinfunction "1_1") (pintype "passive"))
    )
    (net (code "40") (name "RESE'") (class "Default")
      (node (ref "R10") (pin "2") (pinfunction "2_2") (pintype "passive"))
      (node (ref "R8") (pin "2") (pinfunction "2_2") (pintype "passive"))
      (node (ref "SJ1") (pin "2") (pinfunction "2_2") (pintype "passive"))
    )
    (net (code "41") (name "RESET") (class "Default")
      (node (ref "C2") (pin "1") (pinfunction "1_1") (pintype "passive"))
      (node (ref "IC2") (pin "1") (pinfunction "VOUT_1") (pintype "bidirectional"))
      (node (ref "RESET_BUTTON") (pin "3") (pinfunction "3_3") (pintype "passive"))
      (node (ref "RESET_BUTTON") (pin "4") (pinfunction "4_4") (pintype "passive"))
      (node (ref "R_RESET") (pin "2") (pinfunction "2_2") (pintype "passive"))
      (node (ref "U1") (pin "3") (pinfunction "EN_3") (pintype "input"))
    )
    (net (code "42") (name "RTC_RST") (class "Default")
      (node (ref "U1") (pin "16") (pinfunction "IO18_16") (pintype "bidirectional"))
      (node (ref "U4") (pin "4") (pinfunction "~{RST}_4") (pintype "input"))
    )
    (net (code "43") (name "RX") (class "Default")
      (node (ref "TP2") (pin "TP") (pinfunction "TP_TP") (pintype "input"))
      (node (ref "U1") (pin "24") (pinfunction "RXD0/GPIO17_24") (pintype "bidirectional"))
    )
    (net (code "44") (name "SCK") (class "Default")
      (node (ref "D3") (pin "2") (pinfunction "2_2") (pintype "passive"))
      (node (ref "J1") (pin "P5") (pinfunction "CLK_P5") (pintype "bidirectional"))
      (node (ref "J3") (pin "13") (pinfunction "13_13") (pintype "bidirectional"))
      (node (ref "R4") (pin "1") (pinfunction "1_1") (pintype "passive"))
      (node (ref "TP8") (pin "TP") (pinfunction "TP_TP") (pintype "input"))
      (node (ref "U1") (pin "6") (pinfunction "IO6_6") (pintype "bidirectional"))
      (node (ref "U3") (pin "6") (pinfunction "CLK_6") (pintype "input"))
    )
    (net (code "45") (name "SCL") (class "Default")
      (node (ref "J2") (pin "4") (pinfunction "4_4") (pintype "passive"))
      (node (ref "R2-PINH") (pin "1") (pinfunction "1_1") (pintype "passive"))
      (node (ref "SENSOR2") (pin "4") (pinfunction "SCK_4") (pintype "input"))
      (node (ref "U1") (pin "20") (pinfunction "IO22_20") (pintype "bidirectional"))
      (node (ref "U2") (pin "7") (pinfunction "SCL_7") (pintype "input"))
      (node (ref "U4") (pin "16") (pinfunction "SCL_16") (pintype "input"))
    )
    (net (code "46") (name "SDA") (class "Default")
      (node (ref "J2") (pin "3") (pinfunction "3_3") (pintype "passive"))
      (node (ref "R1_PINH") (pin "1") (pinfunction "1_1") (pintype "passive"))
      (node (ref "SENSOR2") (pin "3") (pinfunction "SDI_3") (pintype "bidirectional"))
      (node (ref "U1") (pin "19") (pinfunction "IO21_19") (pintype "bidirectional"))
      (node (ref "U2") (pin "8") (pinfunction "SDA_8") (pintype "bidirectional"))
      (node (ref "U4") (pin "15") (pinfunction "SDA_15") (pintype "bidirectional"))
    )
    (net (code "47") (name "SRC") (class "Default")
      (node (ref "C7") (pin "2") (pinfunction "2_2") (pintype "passive"))
      (node (ref "D8") (pin "2") (pinfunction "A_2") (pintype "bidirectional"))
      (node (ref "L1") (pin "1") (pinfunction "1_1") (pintype "passive"))
      (node (ref "Q2") (pin "3") (pinfunction "D_3") (pintype "bidirectional"))
    )
    (net (code "48") (name "SS_SD") (class "Default")
      (node (ref "D6") (pin "2") (pinfunction "2_2") (pintype "passive"))
      (node (ref "J1") (pin "P2") (pinfunction "CD/DAT3_P2") (pintype "bidirectional"))
      (node (ref "R7") (pin "1") (pinfunction "1_1") (pintype "passive"))
      (node (ref "U1") (pin "4") (pinfunction "IO4_4") (pintype "bidirectional"))
    )
    (net (code "49") (name "TX") (class "Default")
      (node (ref "TP1") (pin "TP") (pinfunction "TP_TP") (pintype "input"))
      (node (ref "U1") (pin "25") (pinfunction "TXD0/GPIO16_25") (pintype "bidirectional"))
    )
    (net (code "50") (name "USB_D+") (class "Default")
      (node (ref "D11") (pin "1") (pinfunction "I/O1_1_1") (pintype "bidirectional"))
      (node (ref "U1") (pin "14") (pinfunction "IO13_14") (pintype "bidirectional"))
    )
    (net (code "51") (name "USB_D-") (class "Default")
      (node (ref "D11") (pin "3") (pinfunction "I/O2_1_3") (pintype "bidirectional"))
      (node (ref "U1") (pin "13") (pinfunction "IO12_13") (pintype "bidirectional"))
    )
    (net (code "52") (name "VBAT") (class "Default")
      (node (ref "C2_BAT") (pin "1") (pinfunction "1_1") (pintype "passive"))
      (node (ref "DMG2305UX-7") (pin "3") (pinfunction "D_3") (pintype "bidirectional"))
      (node (ref "MCP73831") (pin "3") (pinfunction "VBAT_3") (pintype "power_in"))
      (node (ref "TP3") (pin "TP") (pinfunction "TP_TP") (pintype "input"))
      (node (ref "U2") (pin "2") (pinfunction "CELL_2") (pintype "power_in"))
      (node (ref "U2") (pin "3") (pinfunction "VDD_3") (pintype "power_in"))
    )
    (net (code "53") (name "VBUS") (class "Default")
      (node (ref "C1_BAT") (pin "1") (pinfunction "1_1") (pintype "passive"))
      (node (ref "C4_USB") (pin "1") (pinfunction "1_1") (pintype "passive"))
      (node (ref "C5_USB") (pin "1") (pinfunction "1_1") (pintype "passive"))
      (node (ref "CHG_LED") (pin "A") (pinfunction "A_A") (pintype "passive"))
      (node (ref "D11") (pin "5") (pinfunction "VBUS_5") (pintype "bidirectional"))
      (node (ref "DMG2305UX-7") (pin "1") (pinfunction "G_1") (pintype "bidirectional"))
      (node (ref "MCP73831") (pin "4") (pinfunction "VIN_4") (pintype "power_in"))
      (node (ref "PFMF.050.1") (pin "2") (pinfunction "2_2") (pintype "passive"))
      (node (ref "R1_PWRUSB") (pin "2") (pinfunction "2_2") (pintype "passive"))
      (node (ref "SD0805S020S1R0") (pin "2") (pinfunction "ANODE_2") (pintype "bidirectional"))
      (node (ref "TP14") (pin "TP") (pinfunction "TP_TP") (pintype "input"))
    )
    (net (code "54") (name "VRTC") (class "Default")
      (node (ref "C10_SUPERCAP") (pin "2") (pinfunction "2_2") (pintype "passive"))
      (node (ref "C6") (pin "1") (pinfunction "1_1") (pintype "passive"))
      (node (ref "R_CAPACITOR") (pin "1") (pinfunction "1_1") (pintype "passive"))
      (node (ref "U4") (pin "14") (pinfunction "VBAT_14") (pintype "power_in"))
    )
    (net (code "55") (name "VUSB") (class "Default")
      (node (ref "J4") (pin "A4") (pinfunction "A4_A4") (pintype "bidirectional"))
      (node (ref "J4") (pin "A9") (pinfunction "A9_A9") (pintype "bidirectional"))
      (node (ref "J4") (pin "B4") (pinfunction "B4_B4") (pintype "bidirectional"))
      (node (ref "J4") (pin "B9") (pinfunction "B9_B9") (pintype "bidirectional"))
      (node (ref "PFMF.050.1") (pin "1") (pinfunction "1_1") (pintype "passive"))
    )
    (net (code "56") (name "unconnected-(IC1-NC-Pad4)") (class "Default")
      (node (ref "IC1") (pin "4") (pinfunction "NC_4") (pintype "no_connect"))
    )
    (net (code "57") (name "unconnected-(IC2-NC-Pad4)") (class "Default")
      (node (ref "IC2") (pin "4") (pinfunction "NC_4") (pintype "no_connect"))
    )
    (net (code "58") (name "unconnected-(J1-DAT1-PadP8)") (class "Default")
      (node (ref "J1") (pin "P8") (pinfunction "DAT1_P8") (pintype "bidirectional"))
    )
    (net (code "59") (name "unconnected-(J1-DAT2-PadP1)") (class "Default")
      (node (ref "J1") (pin "P1") (pinfunction "DAT2_P1") (pintype "bidirectional"))
    )
    (net (code "60") (name "unconnected-(J1-DETECTION_1-PadS1)") (class "Default")
      (node (ref "J1") (pin "S1") (pinfunction "DETECTION_1_S1") (pintype "bidirectional"))
    )
    (net (code "61") (name "unconnected-(J1-DETECTION_2-PadS2)") (class "Default")
      (node (ref "J1") (pin "S2") (pinfunction "DETECTION_2_S2") (pintype "bidirectional"))
    )
    (net (code "62") (name "unconnected-(J3-Pad1)") (class "Default")
      (node (ref "J3") (pin "1") (pinfunction "1_1") (pintype "bidirectional"))
    )
    (net (code "63") (name "unconnected-(J3-Pad6)") (class "Default")
      (node (ref "J3") (pin "6") (pinfunction "6_6") (pintype "bidirectional"))
    )
    (net (code "64") (name "unconnected-(J3-Pad7)") (class "Default")
      (node (ref "J3") (pin "7") (pinfunction "7_7") (pintype "bidirectional"))
    )
    (net (code "65") (name "unconnected-(J4-PadA8)") (class "Default")
      (node (ref "J4") (pin "A8") (pinfunction "A8_A8") (pintype "bidirectional"))
    )
    (net (code "66") (name "unconnected-(J4-PadB8)") (class "Default")
      (node (ref "J4") (pin "B8") (pinfunction "B8_B8") (pintype "bidirectional"))
    )
    (net (code "67") (name "unconnected-(U1-NC-Pad22)") (class "Default")
      (node (ref "U1") (pin "22") (pinfunction "NC_22") (pintype "no_connect"))
    )
    (net (code "68") (name "unconnected-(U2-~{ALERT}-Pad5)") (class "Default")
      (node (ref "U2") (pin "5") (pinfunction "~{ALERT}_5") (pintype "output"))
    )
  )
)
